# tx_mini_uc_and_tx.net
KiCad netlist of a schematic drawn in Altium Designer
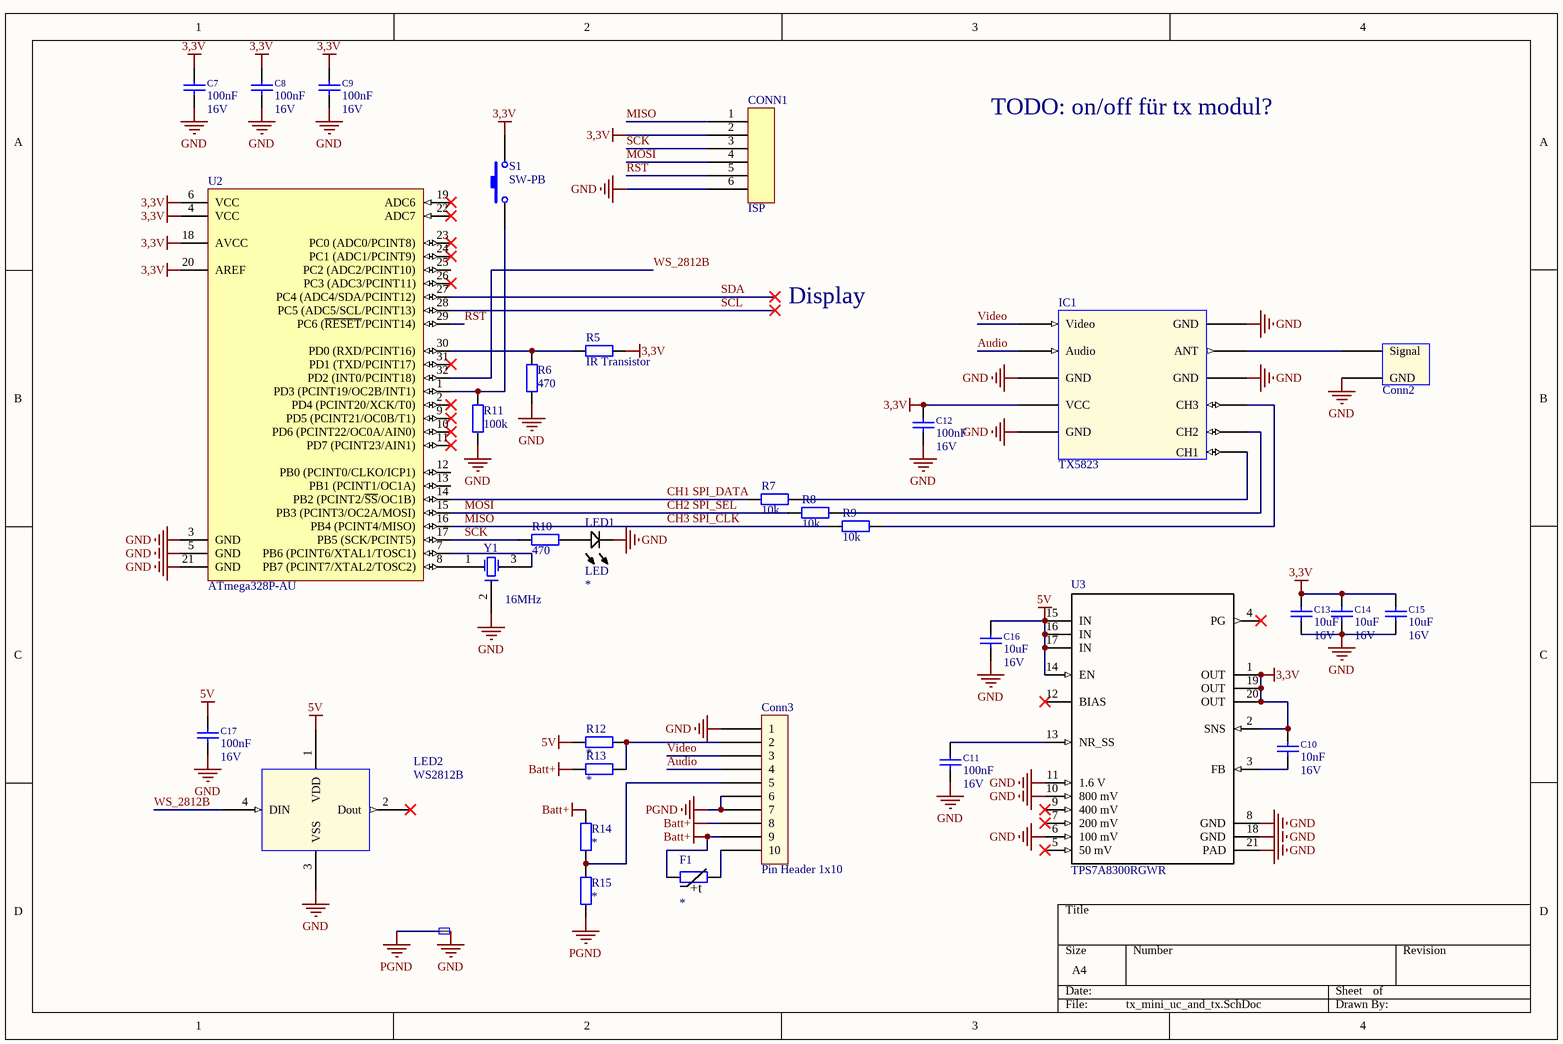
[diagram p0: tx_mini_uc_and_tx.SchDoc]

(export (version "E")
  (design (tool "Eeschema 10.0.6"))
  (components
    (comp (ref "1") (value "Net Tie") (footprint "Net Tie 0201") (libsource (lib "Toni") (part "Net Tie")))
    (comp (ref "C7")
      (value "100nF")
      (footprint "C0402")
      (description "Capacitor")
      (fields (field (name "VOLTAGE") "16V"))
      (libsource (lib "Toni") (part "C 100nF 0402"))
    )
    (comp (ref "C8")
      (value "100nF")
      (footprint "C0402")
      (description "Capacitor")
      (fields (field (name "VOLTAGE") "16V"))
      (libsource (lib "Toni") (part "C 100nF 0402"))
    )
    (comp (ref "C9")
      (value "100nF")
      (footprint "C0402")
      (description "Capacitor")
      (fields (field (name "VOLTAGE") "16V"))
      (libsource (lib "Toni") (part "C 100nF 0402"))
    )
    (comp (ref "C10")
      (value "10nF")
      (footprint "C0402")
      (description "Capacitor")
      (fields (field (name "VOLTAGE") "16V"))
      (libsource (lib "Toni") (part "C"))
    )
    (comp (ref "C11")
      (value "100nF")
      (footprint "C0402")
      (description "Capacitor")
      (fields (field (name "VOLTAGE") "16V"))
      (libsource (lib "Toni") (part "C 100nF 0402"))
    )
    (comp (ref "C12")
      (value "100nF")
      (footprint "C0402")
      (description "Capacitor")
      (fields (field (name "VOLTAGE") "16V"))
      (libsource (lib "Toni") (part "C 100nF 0402"))
    )
    (comp (ref "C13")
      (value "10uF")
      (footprint "C0805")
      (description "Capacitor")
      (fields (field (name "VOLTAGE") "16V"))
      (libsource (lib "Toni") (part "C"))
    )
    (comp (ref "C14")
      (value "10uF")
      (footprint "C0805")
      (description "Capacitor")
      (fields (field (name "VOLTAGE") "16V"))
      (libsource (lib "Toni") (part "C"))
    )
    (comp (ref "C15")
      (value "10uF")
      (footprint "C0805")
      (description "Capacitor")
      (fields (field (name "VOLTAGE") "16V"))
      (libsource (lib "Toni") (part "C"))
    )
    (comp (ref "C16")
      (value "10uF")
      (footprint "C0805")
      (description "Capacitor")
      (fields (field (name "VOLTAGE") "16V"))
      (libsource (lib "Toni") (part "C"))
    )
    (comp (ref "C17")
      (value "100nF")
      (footprint "C0402")
      (description "Capacitor")
      (fields (field (name "VOLTAGE") "16V"))
      (libsource (lib "Toni") (part "C 100nF 0402"))
    )
    (comp (ref "CONN1")
      (value "ISP")
      (footprint "MICRO-MATCH SMD FTE 6")
      (description "Micromatch")
      (libsource (lib "Toni") (part "Micromatch 02x03 SMD"))
    )
    (comp (ref "Conn2") (value "SMA") (footprint "SMA Straight") (libsource (lib "Toni") (part "SMA")))
    (comp (ref "Conn3")
      (value "Pin Header 1x10")
      (footprint "Pin Header 1x10")
      (libsource (lib "Toni") (part "Pin Header 1x10"))
    )
    (comp (ref "F1")
      (value "PTC")
      (footprint "PTC 1812 (4532 metric)")
      (fields (field (name "ALTIUM_VALUE") "*"))
      (libsource (lib "Toni") (part "PTC"))
    )
    (comp (ref "IC1") (value "TX5823") (footprint "Tx5823") (libsource (lib "Toni") (part "TX5823")))
    (comp (ref "LED1")
      (value "LED")
      (footprint "LED-0603-GREEN")
      (fields (field (name "COLOUR") "*"))
      (libsource (lib "Toni") (part "LED"))
    )
    (comp (ref "LED2")
      (value "WS2812B")
      (footprint "WS2812B")
      (description "RGB LED with serial in and out")
      (libsource (lib "Toni") (part "WS2812B"))
    )
    (comp (ref "R5")
      (value "IR Transistor")
      (footprint "RES1206")
      (description "Resistor")
      (fields (field (name "Comment") "R"))
      (libsource (lib "Toni") (part "R"))
    )
    (comp (ref "R6")
      (value "470")
      (footprint "RES0603")
      (description "Resistor")
      (fields (field (name "Comment") "R"))
      (libsource (lib "") (part "R_1"))
    )
    (comp (ref "R7")
      (value "10k")
      (footprint "RES0603")
      (description "Resistor")
      (fields (field (name "Comment") "R"))
      (libsource (lib "Toni") (part "R"))
    )
    (comp (ref "R8")
      (value "10k")
      (footprint "RES0603")
      (description "Resistor")
      (fields (field (name "Comment") "R"))
      (libsource (lib "Toni") (part "R"))
    )
    (comp (ref "R9")
      (value "10k")
      (footprint "RES0603")
      (description "Resistor")
      (fields (field (name "Comment") "R"))
      (libsource (lib "Toni") (part "R"))
    )
    (comp (ref "R10")
      (value "470")
      (footprint "RES0603")
      (description "Resistor")
      (fields (field (name "Comment") "R"))
      (libsource (lib "Toni") (part "R"))
    )
    (comp (ref "R11")
      (value "100k")
      (footprint "RES0603")
      (description "Resistor")
      (fields (field (name "Comment") "R"))
      (libsource (lib "") (part "R_1"))
    )
    (comp (ref "R12")
      (value "R")
      (footprint "RES0603")
      (description "Resistor")
      (fields (field (name "ALTIUM_VALUE") "*"))
      (libsource (lib "Toni") (part "R"))
    )
    (comp (ref "R13")
      (value "R")
      (footprint "RES0603")
      (description "Resistor")
      (fields (field (name "ALTIUM_VALUE") "*"))
      (libsource (lib "Toni") (part "R"))
    )
    (comp (ref "R14")
      (value "R")
      (footprint "RES0603")
      (description "Resistor")
      (fields (field (name "ALTIUM_VALUE") "*"))
      (libsource (lib "") (part "R_1"))
    )
    (comp (ref "R15")
      (value "R")
      (footprint "RES0603")
      (description "Resistor")
      (fields (field (name "ALTIUM_VALUE") "*"))
      (libsource (lib "") (part "R_1"))
    )
    (comp (ref "S1")
      (value "SW-PB")
      (footprint "pushbutton micro switch")
      (description "Switch")
      (fields (field (name "PUBLISHER") "Altium Limited"))
      (libsource (lib "Toni") (part "SW-PB"))
    )
    (comp (ref "U2")
      (value "ATmega328P-AU")
      (footprint "32A_N")
      (fields (field (name "PUBLISHER") "Altium Limited"))
      (libsource (lib "Toni") (part "ATmega328P-AU"))
    )
    (comp (ref "U3")
      (value "TPS7A8300RGWR")
      (footprint "RGW20_N")
      (description "Imported")
      (fields (field (name "PARTNUMBER") "TPS7A8300RGW") (field (name "MANUFACTURER") "Texas Instruments"))
      (libsource (lib "Toni") (part "TPS7A8300RGWR"))
    )
    (comp (ref "Y1")
      (value "Ceramic Resonators CSTCE")
      (footprint "CSTCE")
      (fields (field (name "FREQUENCY") "16MHz"))
      (libsource (lib "Toni") (part "Ceramic Resonators CSTCE"))
    )
  )
  (nets
    (net (code "1") (name "/Audio") (class "Default")
      (node (ref "Conn3") (pin "4") (pinfunction "4_4") (pintype "passive"))
      (node (ref "IC1") (pin "2") (pinfunction "Audio_2") (pintype "input"))
    )
    (net (code "2") (name "/CH1 SPI_DATA") (class "Default")
      (node (ref "R7") (pin "1") (pinfunction "1_1") (pintype "passive"))
      (node (ref "U2") (pin "14") (pinfunction "PB2_(PCINT2/~{SS}/OC1B)_14") (pintype "bidirectional"))
    )
    (net (code "3") (name "/CH2 SPI_SEL") (class "Default")
      (node (ref "CONN1") (pin "4") (pinfunction "*_4") (pintype "passive"))
      (node (ref "R8") (pin "1") (pinfunction "1_1") (pintype "passive"))
      (node (ref "U2") (pin "15") (pinfunction "PB3_(PCINT3/OC2A/MOSI)_15") (pintype "bidirectional"))
    )
    (net (code "4") (name "/CH3 SPI_CLK") (class "Default")
      (node (ref "CONN1") (pin "1") (pinfunction "*_1") (pintype "passive"))
      (node (ref "R9") (pin "1") (pinfunction "1_1") (pintype "passive"))
      (node (ref "U2") (pin "16") (pinfunction "PB4_(PCINT4/MISO)_16") (pintype "bidirectional"))
    )
    (net (code "5") (name "/RST") (class "Default")
      (node (ref "CONN1") (pin "5") (pinfunction "*_5") (pintype "passive"))
      (node (ref "U2") (pin "29") (pinfunction "PC6_(~{RESET}/PCINT14)_29") (pintype "bidirectional"))
    )
    (net (code "6") (name "/SCK") (class "Default")
      (node (ref "CONN1") (pin "3") (pinfunction "*_3") (pintype "passive"))
      (node (ref "R10") (pin "1") (pinfunction "1_1") (pintype "passive"))
      (node (ref "U2") (pin "17") (pinfunction "PB5_(SCK/PCINT5)_17") (pintype "bidirectional"))
    )
    (net (code "7") (name "/SCL") (class "Default")
      (node (ref "U2") (pin "28") (pinfunction "PC5_(ADC5/SCL/PCINT13)_28") (pintype "bidirectional+no_connect"))
    )
    (net (code "8") (name "/SDA") (class "Default")
      (node (ref "U2") (pin "27") (pinfunction "PC4_(ADC4/SDA/PCINT12)_27") (pintype "bidirectional+no_connect"))
    )
    (net (code "9") (name "/Video") (class "Default")
      (node (ref "Conn3") (pin "3") (pinfunction "3_3") (pintype "passive"))
      (node (ref "IC1") (pin "1") (pinfunction "Video_1") (pintype "input"))
    )
    (net (code "10") (name "/WS_2812B") (class "Default")
      (node (ref "LED2") (pin "4") (pinfunction "DIN_4") (pintype "input"))
      (node (ref "U2") (pin "32") (pinfunction "PD2_(INT0/PCINT18)_32") (pintype "bidirectional"))
    )
    (net (code "11") (name "3,3V") (class "Default")
      (node (ref "C10") (pin "1") (pinfunction "1_1") (pintype "passive"))
      (node (ref "C12") (pin "1") (pinfunction "1_1") (pintype "passive"))
      (node (ref "C13") (pin "1") (pinfunction "1_1") (pintype "passive"))
      (node (ref "C14") (pin "1") (pinfunction "1_1") (pintype "passive"))
      (node (ref "C15") (pin "1") (pinfunction "1_1") (pintype "passive"))
      (node (ref "C7") (pin "1") (pinfunction "1_1") (pintype "passive"))
      (node (ref "C8") (pin "1") (pinfunction "1_1") (pintype "passive"))
      (node (ref "C9") (pin "1") (pinfunction "1_1") (pintype "passive"))
      (node (ref "CONN1") (pin "2") (pinfunction "*_2") (pintype "passive"))
      (node (ref "IC1") (pin "4") (pinfunction "VCC_4") (pintype "power_in"))
      (node (ref "R5") (pin "2") (pinfunction "2_2") (pintype "passive"))
      (node (ref "S1") (pin "2") (pinfunction "2_2") (pintype "passive"))
      (node (ref "U2") (pin "18") (pinfunction "AVCC_18") (pintype "power_in"))
      (node (ref "U2") (pin "20") (pinfunction "AREF_20") (pintype "passive"))
      (node (ref "U2") (pin "4") (pinfunction "VCC_4") (pintype "power_in"))
      (node (ref "U2") (pin "6") (pinfunction "VCC_6") (pintype "power_in"))
      (node (ref "U3") (pin "1") (pinfunction "OUT_1") (pintype "power_in"))
      (node (ref "U3") (pin "19") (pinfunction "OUT_19") (pintype "power_in"))
      (node (ref "U3") (pin "2") (pinfunction "SNS_2") (pintype "input"))
      (node (ref "U3") (pin "20") (pinfunction "OUT_20") (pintype "power_in"))
    )
    (net (code "12") (name "5V") (class "Default")
      (node (ref "C16") (pin "1") (pinfunction "1_1") (pintype "passive"))
      (node (ref "C17") (pin "1") (pinfunction "1_1") (pintype "passive"))
      (node (ref "LED2") (pin "1") (pinfunction "VDD_1") (pintype "power_in"))
      (node (ref "R12") (pin "1") (pinfunction "1_1") (pintype "passive"))
      (node (ref "U3") (pin "14") (pinfunction "EN_14") (pintype "input"))
      (node (ref "U3") (pin "15") (pinfunction "IN_15") (pintype "power_in"))
      (node (ref "U3") (pin "16") (pinfunction "IN_16") (pintype "power_in"))
      (node (ref "U3") (pin "17") (pinfunction "IN_17") (pintype "power_in"))
    )
    (net (code "13") (name "Batt+") (class "Default")
      (node (ref "Conn3") (pin "8") (pinfunction "8_8") (pintype "passive"))
      (node (ref "Conn3") (pin "9") (pinfunction "9_9") (pintype "passive"))
      (node (ref "F1") (pin "1") (pinfunction "1_1") (pintype "passive"))
      (node (ref "R13") (pin "1") (pinfunction "1_1") (pintype "passive"))
      (node (ref "R14") (pin "2") (pinfunction "2_2") (pintype "passive"))
    )
    (net (code "14") (name "GND") (class "Default")
      (node (ref "1") (pin "2") (pinfunction "2_2") (pintype "passive"))
      (node (ref "C11") (pin "2") (pinfunction "2_2") (pintype "passive"))
      (node (ref "C12") (pin "2") (pinfunction "2_2") (pintype "passive"))
      (node (ref "C13") (pin "2") (pinfunction "2_2") (pintype "passive"))
      (node (ref "C14") (pin "2") (pinfunction "2_2") (pintype "passive"))
      (node (ref "C15") (pin "2") (pinfunction "2_2") (pintype "passive"))
      (node (ref "C16") (pin "2") (pinfunction "2_2") (pintype "passive"))
      (node (ref "C17") (pin "2") (pinfunction "2_2") (pintype "passive"))
      (node (ref "C7") (pin "2") (pinfunction "2_2") (pintype "passive"))
      (node (ref "C8") (pin "2") (pinfunction "2_2") (pintype "passive"))
      (node (ref "C9") (pin "2") (pinfunction "2_2") (pintype "passive"))
      (node (ref "CONN1") (pin "6") (pinfunction "*_6") (pintype "passive"))
      (node (ref "Conn2") (pin "1") (pinfunction "GND_1") (pintype "passive"))
      (node (ref "Conn3") (pin "1") (pinfunction "1_1") (pintype "passive"))
      (node (ref "IC1") (pin "11") (pinfunction "GND_11") (pintype "power_in"))
      (node (ref "IC1") (pin "3") (pinfunction "GND_3") (pintype "power_in"))
      (node (ref "IC1") (pin "5") (pinfunction "GND_5") (pintype "power_in"))
      (node (ref "IC1") (pin "9") (pinfunction "GND_9") (pintype "power_in"))
      (node (ref "LED1") (pin "K") (pinfunction "K_K") (pintype "passive"))
      (node (ref "LED2") (pin "3") (pinfunction "VSS_3") (pintype "power_in"))
      (node (ref "R11") (pin "1") (pinfunction "1_1") (pintype "passive"))
      (node (ref "R6") (pin "1") (pinfunction "1_1") (pintype "passive"))
      (node (ref "U2") (pin "21") (pinfunction "GND_21") (pintype "power_in"))
      (node (ref "U2") (pin "3") (pinfunction "GND_3") (pintype "power_in"))
      (node (ref "U2") (pin "5") (pinfunction "GND_5") (pintype "power_in"))
      (node (ref "U3") (pin "10") (pinfunction "800_mV_10") (pintype "input"))
      (node (ref "U3") (pin "11") (pinfunction "1.6_V_11") (pintype "input"))
      (node (ref "U3") (pin "18") (pinfunction "GND_18") (pintype "power_in"))
      (node (ref "U3") (pin "21") (pinfunction "PAD_21") (pintype "power_in"))
      (node (ref "U3") (pin "6") (pinfunction "100_mV_6") (pintype "input"))
      (node (ref "U3") (pin "8") (pinfunction "GND_8") (pintype "power_in"))
      (node (ref "Y1") (pin "2") (pinfunction "2_2") (pintype "passive"))
    )
    (net (code "15") (name "Net-(Conn2-Signal)") (class "Default")
      (node (ref "Conn2") (pin "2") (pinfunction "Signal_2") (pintype "passive"))
      (node (ref "IC1") (pin "10") (pinfunction "ANT_10") (pintype "output"))
    )
    (net (code "16") (name "Net-(Conn3-Pad2)") (class "Default")
      (node (ref "Conn3") (pin "2") (pinfunction "2_2") (pintype "passive"))
      (node (ref "R12") (pin "2") (pinfunction "2_2") (pintype "passive"))
      (node (ref "R13") (pin "2") (pinfunction "2_2") (pintype "passive"))
    )
    (net (code "17") (name "Net-(Conn3-Pad5)") (class "Default")
      (node (ref "Conn3") (pin "5") (pinfunction "5_5") (pintype "passive"))
      (node (ref "R14") (pin "1") (pinfunction "1_1") (pintype "passive"))
      (node (ref "R15") (pin "2") (pinfunction "2_2") (pintype "passive"))
    )
    (net (code "18") (name "Net-(Conn3-Pad10)") (class "Default")
      (node (ref "Conn3") (pin "10") (pinfunction "10_10") (pintype "passive"))
      (node (ref "F1") (pin "2") (pinfunction "2_2") (pintype "passive"))
    )
    (net (code "19") (name "Net-(IC1-CH1)") (class "Default")
      (node (ref "IC1") (pin "6") (pinfunction "CH1_6") (pintype "bidirectional"))
      (node (ref "R7") (pin "2") (pinfunction "2_2") (pintype "passive"))
    )
    (net (code "20") (name "Net-(IC1-CH2)") (class "Default")
      (node (ref "IC1") (pin "7") (pinfunction "CH2_7") (pintype "bidirectional"))
      (node (ref "R8") (pin "2") (pinfunction "2_2") (pintype "passive"))
    )
    (net (code "21") (name "Net-(IC1-CH3)") (class "Default")
      (node (ref "IC1") (pin "8") (pinfunction "CH3_8") (pintype "bidirectional"))
      (node (ref "R9") (pin "2") (pinfunction "2_2") (pintype "passive"))
    )
    (net (code "22") (name "Net-(LED1-PadA)") (class "Default")
      (node (ref "LED1") (pin "A") (pinfunction "A_A") (pintype "passive"))
      (node (ref "R10") (pin "2") (pinfunction "2_2") (pintype "passive"))
    )
    (net (code "23") (name "Net-(U2-PB6_(PCINT6{slash}XTAL1{slash}TOSC1))") (class "Default")
      (node (ref "U2") (pin "7") (pinfunction "PB6_(PCINT6/XTAL1/TOSC1)_7") (pintype "bidirectional"))
      (node (ref "Y1") (pin "3") (pinfunction "3_3") (pintype "passive"))
    )
    (net (code "24") (name "Net-(U2-PB7_(PCINT7{slash}XTAL2{slash}TOSC2))") (class "Default")
      (node (ref "U2") (pin "8") (pinfunction "PB7_(PCINT7/XTAL2/TOSC2)_8") (pintype "bidirectional"))
      (node (ref "Y1") (pin "1") (pinfunction "1_1") (pintype "passive"))
    )
    (net (code "25") (name "Net-(U2-PD0_(RXD{slash}PCINT16))") (class "Default")
      (node (ref "R5") (pin "1") (pinfunction "1_1") (pintype "passive"))
      (node (ref "R6") (pin "2") (pinfunction "2_2") (pintype "passive"))
      (node (ref "U2") (pin "30") (pinfunction "PD0_(RXD/PCINT16)_30") (pintype "bidirectional"))
    )
    (net (code "26") (name "Net-(U2-PD3_(PCINT19{slash}OC2B{slash}INT1))") (class "Default")
      (node (ref "R11") (pin "2") (pinfunction "2_2") (pintype "passive"))
      (node (ref "S1") (pin "1") (pinfunction "1_1") (pintype "passive"))
      (node (ref "U2") (pin "1") (pinfunction "PD3_(PCINT19/OC2B/INT1)_1") (pintype "bidirectional"))
    )
    (net (code "27") (name "Net-(U3-FB)") (class "Default")
      (node (ref "C10") (pin "2") (pinfunction "2_2") (pintype "passive"))
      (node (ref "U3") (pin "3") (pinfunction "FB_3") (pintype "input"))
    )
    (net (code "28") (name "Net-(U3-NR_SS)") (class "Default")
      (node (ref "C11") (pin "1") (pinfunction "1_1") (pintype "passive"))
      (node (ref "U3") (pin "13") (pinfunction "NR_SS_13") (pintype "input"))
    )
    (net (code "29") (name "PGND") (class "Default")
      (node (ref "1") (pin "1") (pinfunction "1_1") (pintype "passive"))
      (node (ref "Conn3") (pin "6") (pinfunction "6_6") (pintype "passive"))
      (node (ref "Conn3") (pin "7") (pinfunction "7_7") (pintype "passive"))
      (node (ref "R15") (pin "1") (pinfunction "1_1") (pintype "passive"))
    )
    (net (code "30") (name "unconnected-(LED2-Dout-Pad2)") (class "Default")
      (node (ref "LED2") (pin "2") (pinfunction "Dout_2") (pintype "output+no_connect"))
    )
    (net (code "31") (name "unconnected-(U2-ADC6-Pad19)") (class "Default")
      (node (ref "U2") (pin "19") (pinfunction "ADC6_19") (pintype "input+no_connect"))
    )
    (net (code "32") (name "unconnected-(U2-ADC7-Pad22)") (class "Default")
      (node (ref "U2") (pin "22") (pinfunction "ADC7_22") (pintype "input+no_connect"))
    )
    (net (code "33") (name "unconnected-(U2-PB0_(PCINT0{slash}CLKO{slash}ICP1)-Pad12)") (class "Default")
      (node (ref "U2") (pin "12") (pinfunction "PB0_(PCINT0/CLKO/ICP1)_12") (pintype "bidirectional"))
    )
    (net (code "34") (name "unconnected-(U2-PB1_(PCINT1{slash}OC1A)-Pad13)") (class "Default")
      (node (ref "U2") (pin "13") (pinfunction "PB1_(PCINT1/OC1A)_13") (pintype "bidirectional"))
    )
    (net (code "35") (name "unconnected-(U2-PC0_(ADC0{slash}PCINT8)-Pad23)") (class "Default")
      (node (ref "U2") (pin "23") (pinfunction "PC0_(ADC0/PCINT8)_23") (pintype "bidirectional+no_connect"))
    )
    (net (code "36") (name "unconnected-(U2-PC1_(ADC1{slash}PCINT9)-Pad24)") (class "Default")
      (node (ref "U2") (pin "24") (pinfunction "PC1_(ADC1/PCINT9)_24") (pintype "bidirectional+no_connect"))
    )
    (net (code "37") (name "unconnected-(U2-PC2_(ADC2{slash}PCINT10)-Pad25)") (class "Default")
      (node (ref "U2") (pin "25") (pinfunction "PC2_(ADC2/PCINT10)_25") (pintype "bidirectional"))
    )
    (net (code "38") (name "unconnected-(U2-PC3_(ADC3{slash}PCINT11)-Pad26)") (class "Default")
      (node (ref "U2") (pin "26") (pinfunction "PC3_(ADC3/PCINT11)_26") (pintype "bidirectional+no_connect"))
    )
    (net (code "39") (name "unconnected-(U2-PD1_(TXD{slash}PCINT17)-Pad31)") (class "Default")
      (node (ref "U2") (pin "31") (pinfunction "PD1_(TXD/PCINT17)_31") (pintype "bidirectional+no_connect"))
    )
    (net (code "40") (name "unconnected-(U2-PD4_(PCINT20{slash}XCK{slash}T0)-Pad2)") (class "Default")
      (node (ref "U2") (pin "2") (pinfunction "PD4_(PCINT20/XCK/T0)_2") (pintype "bidirectional+no_connect"))
    )
    (net (code "41") (name "unconnected-(U2-PD5_(PCINT21{slash}OC0B{slash}T1)-Pad9)") (class "Default")
      (node (ref "U2") (pin "9") (pinfunction "PD5_(PCINT21/OC0B/T1)_9") (pintype "bidirectional+no_connect"))
    )
    (net (code "42") (name "unconnected-(U2-PD6_(PCINT22{slash}OC0A{slash}AIN0)-Pad10)") (class "Default")
      (node (ref "U2") (pin "10") (pinfunction "PD6_(PCINT22/OC0A/AIN0)_10") (pintype "bidirectional+no_connect"))
    )
    (net (code "43") (name "unconnected-(U2-PD7_(PCINT23{slash}AIN1)-Pad11)") (class "Default")
      (node (ref "U2") (pin "11") (pinfunction "PD7_(PCINT23/AIN1)_11") (pintype "bidirectional+no_connect"))
    )
    (net (code "44") (name "unconnected-(U3-50_mV-Pad5)") (class "Default")
      (node (ref "U3") (pin "5") (pinfunction "50_mV_5") (pintype "input+no_connect"))
    )
    (net (code "45") (name "unconnected-(U3-200_mV-Pad7)") (class "Default")
      (node (ref "U3") (pin "7") (pinfunction "200_mV_7") (pintype "input+no_connect"))
    )
    (net (code "46") (name "unconnected-(U3-400_mV-Pad9)") (class "Default")
      (node (ref "U3") (pin "9") (pinfunction "400_mV_9") (pintype "input+no_connect"))
    )
    (net (code "47") (name "unconnected-(U3-BIAS-Pad12)") (class "Default")
      (node (ref "U3") (pin "12") (pinfunction "BIAS_12") (pintype "power_in+no_connect"))
    )
    (net (code "48") (name "unconnected-(U3-PG-Pad4)") (class "Default")
      (node (ref "U3") (pin "4") (pinfunction "PG_4") (pintype "output+no_connect"))
    )
  )
)
